# source_eagle.net
KiCad netlist of a schematic drawn in EAGLE
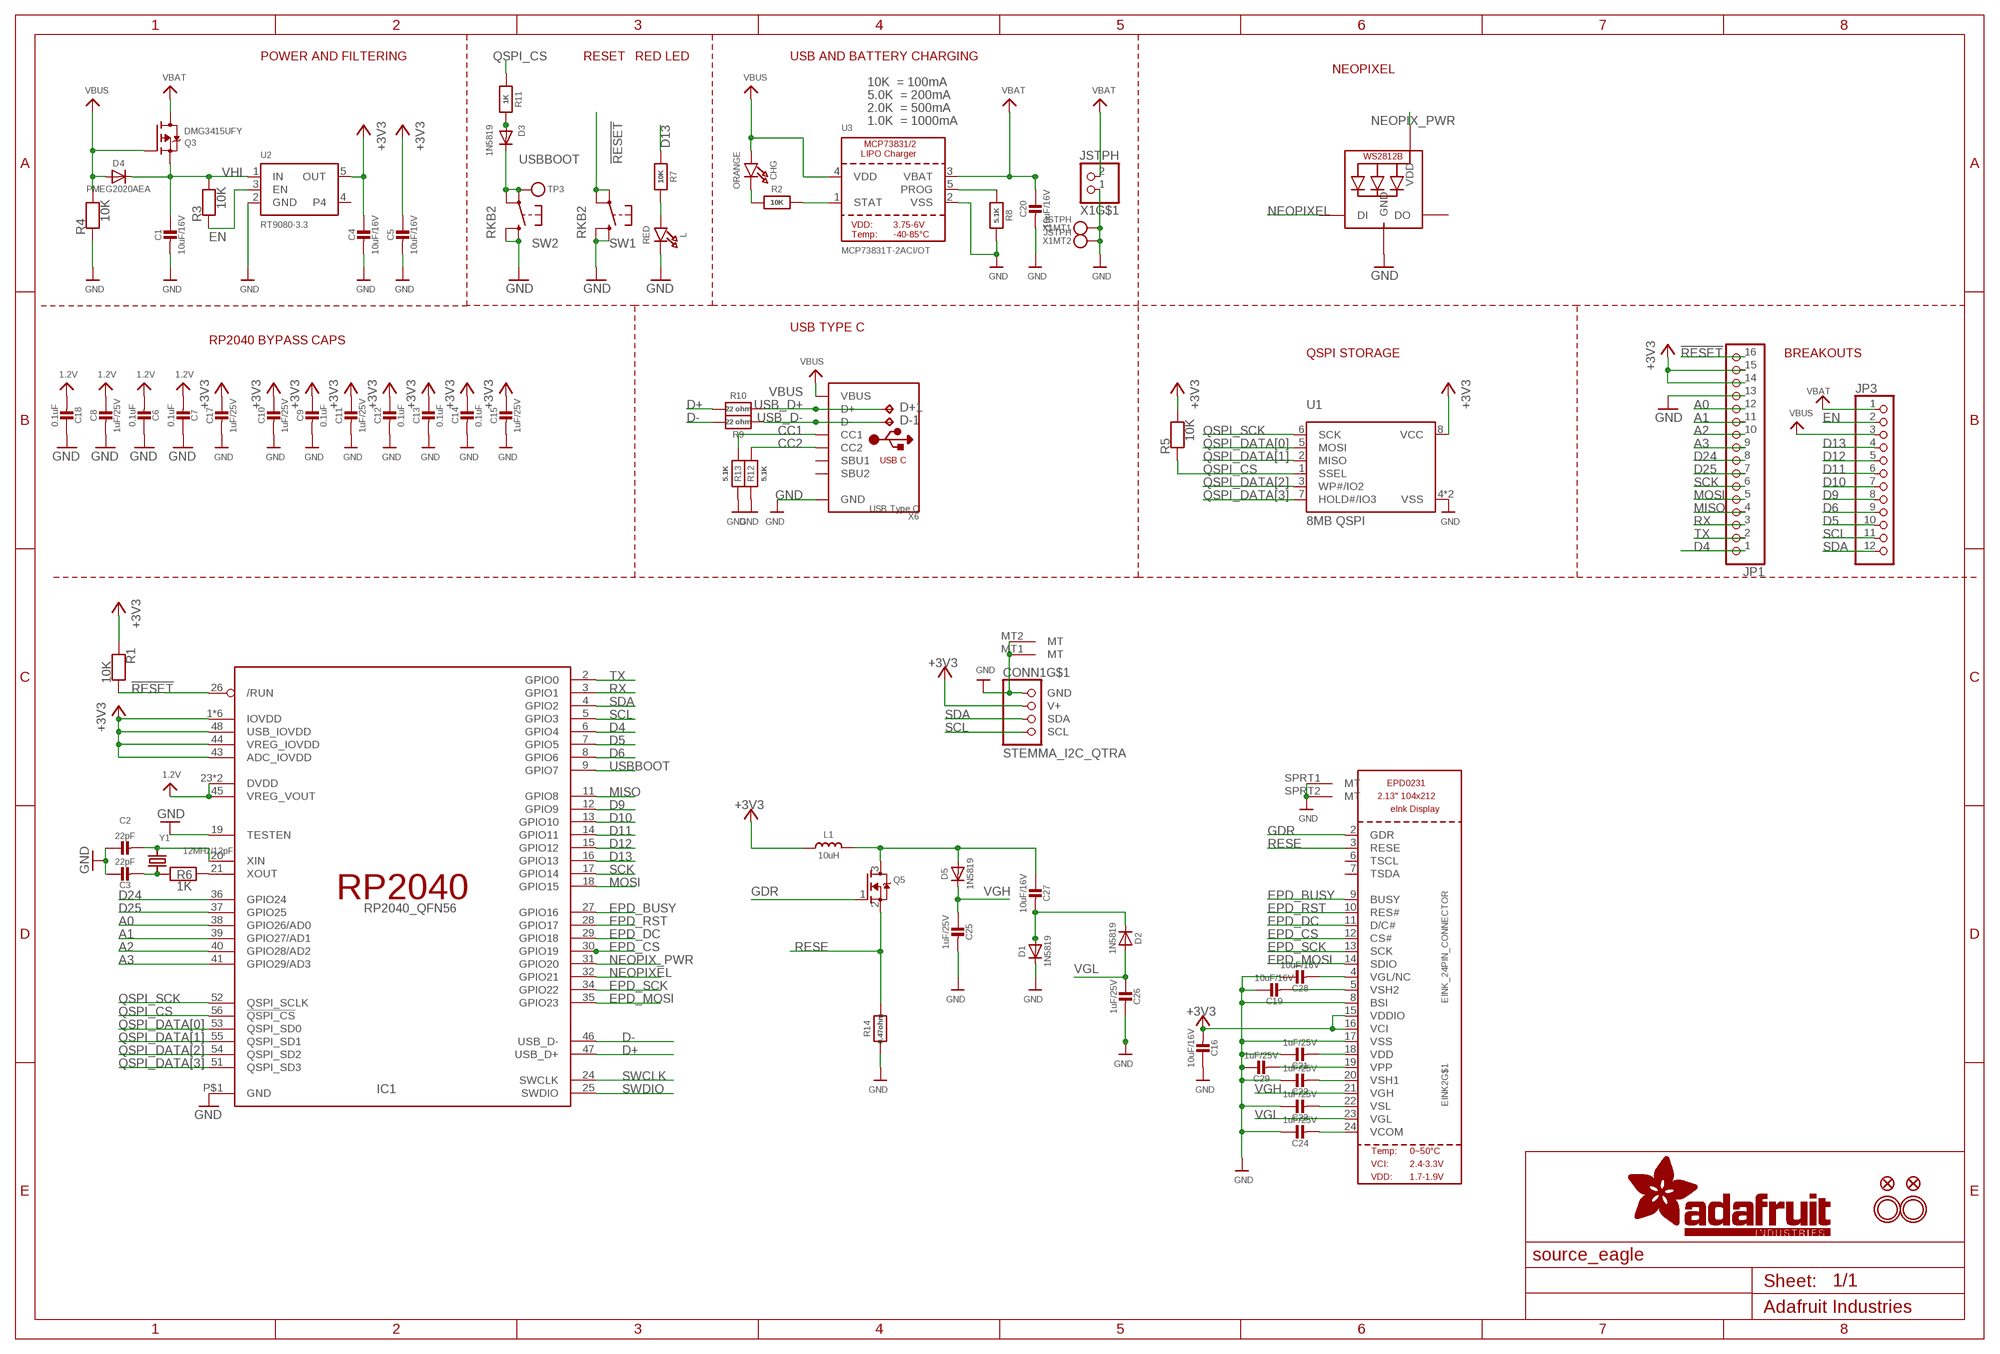
[diagram p0: schematic, sheet 1]

(export (version "E")
  (design (tool "Eeschema 10.0.6"))
  (components
    (comp (ref "C1")
      (value "10uF/16V")
      (footprint "eagle-import:0805-NO")
      (libsource (lib "eagle-import") (part "CAP_CERAMIC0805-NOOUTLINE"))
    )
    (comp (ref "C2")
      (value "22pF")
      (footprint "eagle-import:_0402NO")
      (libsource (lib "eagle-import") (part "CAP_CERAMIC_0402NO"))
    )
    (comp (ref "C3")
      (value "22pF")
      (footprint "eagle-import:_0402NO")
      (libsource (lib "eagle-import") (part "CAP_CERAMIC_0402NO"))
    )
    (comp (ref "C4")
      (value "10uF/16V")
      (footprint "eagle-import:0805-NO")
      (fields (field (name "REV") "A"))
      (libsource (lib "eagle-import") (part "CAP_CERAMIC0805-NOOUTLINE"))
    )
    (comp (ref "C5")
      (value "10uF/16V")
      (footprint "eagle-import:0805-NO")
      (libsource (lib "eagle-import") (part "CAP_CERAMIC0805-NOOUTLINE"))
    )
    (comp (ref "C6")
      (value "0.1uF")
      (footprint "eagle-import:_0402NO")
      (libsource (lib "eagle-import") (part "CAP_CERAMIC_0402NO"))
    )
    (comp (ref "C7")
      (value "0.1uF")
      (footprint "eagle-import:_0402NO")
      (libsource (lib "eagle-import") (part "CAP_CERAMIC_0402NO"))
    )
    (comp (ref "C8")
      (value "1uF/25V")
      (footprint "eagle-import:_0402NO")
      (libsource (lib "eagle-import") (part "CAP_CERAMIC_0402NO"))
    )
    (comp (ref "C9")
      (value "0.1uF")
      (footprint "eagle-import:_0402NO")
      (libsource (lib "eagle-import") (part "CAP_CERAMIC_0402NO"))
    )
    (comp (ref "C10")
      (value "1uF/25V")
      (footprint "eagle-import:_0402NO")
      (libsource (lib "eagle-import") (part "CAP_CERAMIC_0402NO"))
    )
    (comp (ref "C11")
      (value "1uF/25V")
      (footprint "eagle-import:_0402NO")
      (libsource (lib "eagle-import") (part "CAP_CERAMIC_0402NO"))
    )
    (comp (ref "C12")
      (value "0.1uF")
      (footprint "eagle-import:_0402NO")
      (libsource (lib "eagle-import") (part "CAP_CERAMIC_0402NO"))
    )
    (comp (ref "C13")
      (value "0.1uF")
      (footprint "eagle-import:_0402NO")
      (libsource (lib "eagle-import") (part "CAP_CERAMIC_0402NO"))
    )
    (comp (ref "C14")
      (value "0.1uF")
      (footprint "eagle-import:_0402NO")
      (libsource (lib "eagle-import") (part "CAP_CERAMIC_0402NO"))
    )
    (comp (ref "C15")
      (value "1uF/25V")
      (footprint "eagle-import:_0402NO")
      (libsource (lib "eagle-import") (part "CAP_CERAMIC_0402NO"))
    )
    (comp (ref "C16")
      (value "10uF/16V")
      (footprint "eagle-import:0805-NO")
      (libsource (lib "eagle-import") (part "CAP_CERAMIC0805-NOOUTLINE"))
    )
    (comp (ref "C17")
      (value "1uF/25V")
      (footprint "eagle-import:_0402NO")
      (libsource (lib "eagle-import") (part "CAP_CERAMIC_0402NO"))
    )
    (comp (ref "C18")
      (value "0.1uF")
      (footprint "eagle-import:_0402NO")
      (libsource (lib "eagle-import") (part "CAP_CERAMIC_0402NO"))
    )
    (comp (ref "C19")
      (value "10uF/16V")
      (footprint "eagle-import:0805-NO")
      (libsource (lib "eagle-import") (part "CAP_CERAMIC0805-NOOUTLINE"))
    )
    (comp (ref "C20")
      (value "10uF/16V")
      (footprint "eagle-import:0805-NO")
      (libsource (lib "eagle-import") (part "CAP_CERAMIC0805-NOOUTLINE"))
    )
    (comp (ref "C21")
      (value "1uF/25V")
      (footprint "eagle-import:_0402NO")
      (libsource (lib "eagle-import") (part "CAP_CERAMIC_0402NO"))
    )
    (comp (ref "C22")
      (value "1uF/25V")
      (footprint "eagle-import:_0402NO")
      (libsource (lib "eagle-import") (part "CAP_CERAMIC_0402NO"))
    )
    (comp (ref "C23")
      (value "1uF/25V")
      (footprint "eagle-import:_0402NO")
      (libsource (lib "eagle-import") (part "CAP_CERAMIC_0402NO"))
    )
    (comp (ref "C24")
      (value "1uF/25V")
      (footprint "eagle-import:_0402NO")
      (libsource (lib "eagle-import") (part "CAP_CERAMIC_0402NO"))
    )
    (comp (ref "C25")
      (value "1uF/25V")
      (footprint "eagle-import:_0402NO")
      (libsource (lib "eagle-import") (part "CAP_CERAMIC_0402NO"))
    )
    (comp (ref "C26")
      (value "1uF/25V")
      (footprint "eagle-import:_0402NO")
      (libsource (lib "eagle-import") (part "CAP_CERAMIC_0402NO"))
    )
    (comp (ref "C27")
      (value "10uF/16V")
      (footprint "eagle-import:0805-NO")
      (libsource (lib "eagle-import") (part "CAP_CERAMIC0805-NOOUTLINE"))
    )
    (comp (ref "C28")
      (value "10uF/16V")
      (footprint "eagle-import:0805-NO")
      (libsource (lib "eagle-import") (part "CAP_CERAMIC0805-NOOUTLINE"))
    )
    (comp (ref "C29")
      (value "1uF/25V")
      (footprint "eagle-import:_0402NO")
      (libsource (lib "eagle-import") (part "CAP_CERAMIC_0402NO"))
    )
    (comp (ref "CHG")
      (value "ORANGE")
      (footprint "eagle-import:CHIPLED_0603_NOOUTLINE")
      (libsource (lib "eagle-import") (part "LED0603_NOOUTLINE"))
    )
    (comp (ref "CONN1")
      (value "STEMMA_I2C_QTRA")
      (footprint "eagle-import:JST_SH4_RA")
      (libsource (lib "eagle-import") (part "STEMMA_I2C_QTRA"))
    )
    (comp (ref "D+1")
      (value "TPB1,27")
      (footprint "eagle-import:B1,27")
      (libsource (lib "eagle-import") (part "TPB1,27"))
    )
    (comp (ref "D-1")
      (value "TPB1,27")
      (footprint "eagle-import:B1,27")
      (libsource (lib "eagle-import") (part "TPB1,27"))
    )
    (comp (ref "D1")
      (value "1N5819")
      (footprint "eagle-import:SOD-323_MINI")
      (libsource (lib "eagle-import") (part "DIODE_SOD323MINI"))
    )
    (comp (ref "D2")
      (value "1N5819")
      (footprint "eagle-import:SOD-323_MINI")
      (libsource (lib "eagle-import") (part "DIODE_SOD323MINI"))
    )
    (comp (ref "D3")
      (value "1N5819")
      (footprint "eagle-import:SOD-323_MINI")
      (libsource (lib "eagle-import") (part "DIODE_SOD323MINI"))
    )
    (comp (ref "D4")
      (value "PMEG2020AEA")
      (footprint "eagle-import:SOD-323F")
      (libsource (lib "eagle-import") (part "DIODESOD-323F"))
    )
    (comp (ref "D5")
      (value "1N5819")
      (footprint "eagle-import:SOD-323_MINI")
      (libsource (lib "eagle-import") (part "DIODE_SOD323MINI"))
    )
    (comp (ref "EINK2")
      (value "EINK_24PIN_CONNECTOR")
      (footprint "eagle-import:EINK_24PIN")
      (libsource (lib "eagle-import") (part "EINK_24PIN_CONNECTOR"))
    )
    (comp (ref "IC1")
      (value "RP2040_QFN56")
      (footprint "eagle-import:QFN56_7MM_REDUCEDEPAD")
      (libsource (lib "eagle-import") (part "RP2040_QFN56"))
    )
    (comp (ref "JP1")
      (value "HEADER-1X16ROUND")
      (footprint "eagle-import:1X16_ROUND")
      (libsource (lib "eagle-import") (part "HEADER-1X16ROUND"))
    )
    (comp (ref "JP3")
      (value "HEADER-1X12")
      (footprint "eagle-import:1X12_ROUND")
      (libsource (lib "eagle-import") (part "HEADER-1X12"))
    )
    (comp (ref "L")
      (value "RED")
      (footprint "eagle-import:CHIPLED_0603_NOOUTLINE")
      (libsource (lib "eagle-import") (part "LED0603_NOOUTLINE"))
    )
    (comp (ref "L1")
      (value "10uH")
      (footprint "eagle-import:INDUCTOR_4X4MM_NR401")
      (libsource (lib "eagle-import") (part "INDUCTORNR401"))
    )
    (comp (ref "LED1")
      (value "WS2812B_SK6805_1515")
      (footprint "eagle-import:SK6805_1515")
      (libsource (lib "eagle-import") (part "WS2812B_SK6805_1515"))
    )
    (comp (ref "Q3")
      (value "DMG3415UFY")
      (footprint "eagle-import:DFN2015-3")
      (libsource (lib "eagle-import") (part "MOSFET-P_DFN2015"))
    )
    (comp (ref "Q5")
      (value "IRLML0100")
      (footprint "eagle-import:SOT23-WIDE")
      (libsource (lib "eagle-import") (part "MOSFET-NWIDE"))
    )
    (comp (ref "R1")
      (value "10K")
      (footprint "eagle-import:_0402NO")
      (libsource (lib "eagle-import") (part "RESISTOR_0402NO"))
    )
    (comp (ref "R2")
      (value "10K")
      (footprint "eagle-import:_0402NO")
      (libsource (lib "eagle-import") (part "RESISTOR_0402NO"))
    )
    (comp (ref "R3")
      (value "10K")
      (footprint "eagle-import:_0402NO")
      (libsource (lib "eagle-import") (part "RESISTOR_0402NO"))
    )
    (comp (ref "R4")
      (value "10K")
      (footprint "eagle-import:_0402NO")
      (libsource (lib "eagle-import") (part "RESISTOR_0402NO"))
    )
    (comp (ref "R5")
      (value "10K")
      (footprint "eagle-import:_0402NO")
      (libsource (lib "eagle-import") (part "RESISTOR_0402NO"))
    )
    (comp (ref "R6")
      (value "1K")
      (footprint "eagle-import:_0402NO")
      (libsource (lib "eagle-import") (part "RESISTOR_0402NO"))
    )
    (comp (ref "R7")
      (value "10K")
      (footprint "eagle-import:_0402NO")
      (libsource (lib "eagle-import") (part "RESISTOR_0402NO"))
    )
    (comp (ref "R8")
      (value "5.1K")
      (footprint "eagle-import:_0402NO")
      (libsource (lib "eagle-import") (part "RESISTOR_0402NO"))
    )
    (comp (ref "R9")
      (value "22 ohm")
      (footprint "eagle-import:_0402NO")
      (libsource (lib "eagle-import") (part "RESISTOR_0402NO"))
    )
    (comp (ref "R10")
      (value "22 ohm")
      (footprint "eagle-import:_0402NO")
      (libsource (lib "eagle-import") (part "RESISTOR_0402NO"))
    )
    (comp (ref "R11")
      (value "1K")
      (footprint "eagle-import:_0402NO")
      (libsource (lib "eagle-import") (part "RESISTOR_0402NO"))
    )
    (comp (ref "R12")
      (value "5.1K")
      (footprint "eagle-import:_0402NO")
      (libsource (lib "eagle-import") (part "RESISTOR_0402NO"))
    )
    (comp (ref "R13")
      (value "5.1K")
      (footprint "eagle-import:_0402NO")
      (libsource (lib "eagle-import") (part "RESISTOR_0402NO"))
    )
    (comp (ref "R14")
      (value "0.47ohm")
      (footprint "eagle-import:0603-NO")
      (libsource (lib "eagle-import") (part "RESISTOR_0603_NOOUT"))
    )
    (comp (ref "SW1")
      (value "RKB2")
      (footprint "eagle-import:BTN_RKB2_4.6X2.8")
      (libsource (lib "eagle-import") (part "SWITCH_TACT_SMT_RKB2"))
    )
    (comp (ref "SW2")
      (value "RKB2")
      (footprint "eagle-import:BTN_RKB2_4.6X2.8")
      (libsource (lib "eagle-import") (part "SWITCH_TACT_SMT_RKB2"))
    )
    (comp (ref "TP3")
      (value "TESTPOINTROUND1.5MMNO")
      (footprint "eagle-import:TESTPOINT_ROUND_1.5MM_NO")
      (libsource (lib "eagle-import") (part "TESTPOINTROUND1.5MMNO"))
    )
    (comp (ref "U$31")
      (value "MOUNTINGHOLE2.5")
      (footprint "eagle-import:MOUNTINGHOLE_2.5_PLATED")
      (libsource (lib "eagle-import") (part "MOUNTINGHOLE2.5"))
    )
    (comp (ref "U$32")
      (value "MOUNTINGHOLE2.5")
      (footprint "eagle-import:MOUNTINGHOLE_2.5_PLATED")
      (libsource (lib "eagle-import") (part "MOUNTINGHOLE2.5"))
    )
    (comp (ref "U$34")
      (value "FIDUCIAL_1MM")
      (footprint "eagle-import:FIDUCIAL_1MM")
      (libsource (lib "eagle-import") (part "FIDUCIAL_1MM"))
    )
    (comp (ref "U$35")
      (value "FIDUCIAL_1MM")
      (footprint "eagle-import:FIDUCIAL_1MM")
      (libsource (lib "eagle-import") (part "FIDUCIAL_1MM"))
    )
    (comp (ref "U1")
      (value "8MB QSPI")
      (footprint "eagle-import:USON8_4X4")
      (libsource (lib "eagle-import") (part "SPIFLASH_8PIN_4X4"))
    )
    (comp (ref "U2")
      (value "RT9080-3.3")
      (footprint "eagle-import:SOT23-5")
      (fields (field (name "JLC_ROTATION") "0"))
      (libsource (lib "eagle-import") (part "VREG_SOT23-5"))
    )
    (comp (ref "U3")
      (value "MCP73831T-2ACI/OT")
      (footprint "eagle-import:SOT23-5")
      (libsource (lib "eagle-import") (part "MCP73831/2"))
    )
    (comp (ref "X1")
      (value "JSTPH")
      (footprint "eagle-import:JSTPH2_BATT")
      (libsource (lib "eagle-import") (part "CON_JST_PH_2PIN_MT_BATT"))
    )
    (comp (ref "X6")
      (value "USB Type C")
      (footprint "eagle-import:USB_C_CUSB31-CFM2AX-01-X")
      (libsource (lib "eagle-import") (part "USB_C"))
    )
    (comp (ref "Y1")
      (value "12MHz/12pF")
      (footprint "eagle-import:CRYSTAL_2.5X2")
      (libsource (lib "eagle-import") (part "CRYSTAL2.5X2.0"))
    )
  )
  (nets
    (net (code "1") (name "+3V3") (class "Default")
      (node (ref "C10") (pin "1") (pinfunction "1_1") (pintype "passive"))
      (node (ref "C11") (pin "1") (pinfunction "1_1") (pintype "passive"))
      (node (ref "C12") (pin "1") (pinfunction "1_1") (pintype "passive"))
      (node (ref "C13") (pin "1") (pinfunction "1_1") (pintype "passive"))
      (node (ref "C14") (pin "1") (pinfunction "1_1") (pintype "passive"))
      (node (ref "C15") (pin "1") (pinfunction "1_1") (pintype "passive"))
      (node (ref "C16") (pin "2") (pinfunction "2_2") (pintype "passive"))
      (node (ref "C17") (pin "1") (pinfunction "1_1") (pintype "passive"))
      (node (ref "C4") (pin "1") (pinfunction "1_1") (pintype "passive"))
      (node (ref "C5") (pin "1") (pinfunction "1_1") (pintype "passive"))
      (node (ref "C9") (pin "1") (pinfunction "1_1") (pintype "passive"))
      (node (ref "CONN1") (pin "2") (pinfunction "V+_2") (pintype "passive"))
      (node (ref "EINK2") (pin "15") (pinfunction "VDDIO_15") (pintype "power_in"))
      (node (ref "EINK2") (pin "16") (pinfunction "VCI_16") (pintype "power_in"))
      (node (ref "IC1") (pin "1") (pinfunction "IOVDD_1") (pintype "power_in"))
      (node (ref "IC1") (pin "10") (pinfunction "IOVDD_10") (pintype "power_in"))
      (node (ref "IC1") (pin "22") (pinfunction "IOVDD_22") (pintype "power_in"))
      (node (ref "IC1") (pin "33") (pinfunction "IOVDD_33") (pintype "power_in"))
      (node (ref "IC1") (pin "42") (pinfunction "IOVDD_42") (pintype "power_in"))
      (node (ref "IC1") (pin "43") (pinfunction "ADC_IOVDD_43") (pintype "power_in"))
      (node (ref "IC1") (pin "44") (pinfunction "VREG_IOVDD_44") (pintype "power_in"))
      (node (ref "IC1") (pin "48") (pinfunction "USB_IOVDD_48") (pintype "power_in"))
      (node (ref "IC1") (pin "49") (pinfunction "IOVDD_49") (pintype "power_in"))
      (node (ref "JP1") (pin "14") (pinfunction "14_14") (pintype "passive"))
      (node (ref "JP1") (pin "15") (pinfunction "15_15") (pintype "passive"))
      (node (ref "L1") (pin "P$2") (pinfunction "2_P$2") (pintype "passive"))
      (node (ref "R1") (pin "1") (pinfunction "1_1") (pintype "passive"))
      (node (ref "R5") (pin "2") (pinfunction "2_2") (pintype "passive"))
      (node (ref "U1") (pin "8") (pinfunction "VCC_8") (pintype "bidirectional"))
      (node (ref "U2") (pin "5") (pinfunction "OUT_5") (pintype "power_in"))
    )
    (net (code "2") (name "/A0") (class "Default")
      (node (ref "IC1") (pin "38") (pinfunction "GPIO26/AD0_38") (pintype "bidirectional"))
      (node (ref "JP1") (pin "12") (pinfunction "12_12") (pintype "passive"))
    )
    (net (code "3") (name "/A1") (class "Default")
      (node (ref "IC1") (pin "39") (pinfunction "GPIO27/AD1_39") (pintype "bidirectional"))
      (node (ref "JP1") (pin "11") (pinfunction "11_11") (pintype "passive"))
    )
    (net (code "4") (name "/A2") (class "Default")
      (node (ref "IC1") (pin "40") (pinfunction "GPIO28/AD2_40") (pintype "bidirectional"))
      (node (ref "JP1") (pin "10") (pinfunction "10_10") (pintype "passive"))
    )
    (net (code "5") (name "/A3") (class "Default")
      (node (ref "IC1") (pin "41") (pinfunction "GPIO29/AD3_41") (pintype "bidirectional"))
      (node (ref "JP1") (pin "9") (pinfunction "9_9") (pintype "passive"))
    )
    (net (code "6") (name "/CC1") (class "Default")
      (node (ref "R13") (pin "2") (pinfunction "2_2") (pintype "passive"))
      (node (ref "X6") (pin "A5") (pinfunction "CC1_A5") (pintype "bidirectional"))
    )
    (net (code "7") (name "/CC2") (class "Default")
      (node (ref "R12") (pin "2") (pinfunction "2_2") (pintype "passive"))
      (node (ref "X6") (pin "B5") (pinfunction "CC2_B5") (pintype "bidirectional"))
    )
    (net (code "8") (name "/D+") (class "Default")
      (node (ref "IC1") (pin "47") (pinfunction "USB_D+_47") (pintype "bidirectional"))
      (node (ref "R10") (pin "2") (pinfunction "2_2") (pintype "passive"))
    )
    (net (code "9") (name "/D-") (class "Default")
      (node (ref "IC1") (pin "46") (pinfunction "USB_D-_46") (pintype "bidirectional"))
      (node (ref "R9") (pin "2") (pinfunction "2_2") (pintype "passive"))
    )
    (net (code "10") (name "/D4") (class "Default")
      (node (ref "IC1") (pin "6") (pinfunction "GPIO4_6") (pintype "bidirectional"))
      (node (ref "JP1") (pin "1") (pinfunction "1_1") (pintype "passive"))
    )
    (net (code "11") (name "/D5") (class "Default")
      (node (ref "IC1") (pin "7") (pinfunction "GPIO5_7") (pintype "bidirectional"))
      (node (ref "JP3") (pin "10") (pinfunction "10_10") (pintype "passive"))
    )
    (net (code "12") (name "/D6") (class "Default")
      (node (ref "IC1") (pin "8") (pinfunction "GPIO6_8") (pintype "bidirectional"))
      (node (ref "JP3") (pin "9") (pinfunction "9_9") (pintype "passive"))
    )
    (net (code "13") (name "/D9") (class "Default")
      (node (ref "IC1") (pin "12") (pinfunction "GPIO9_12") (pintype "bidirectional"))
      (node (ref "JP3") (pin "8") (pinfunction "8_8") (pintype "passive"))
    )
    (net (code "14") (name "/D10") (class "Default")
      (node (ref "IC1") (pin "13") (pinfunction "GPIO10_13") (pintype "bidirectional"))
      (node (ref "JP3") (pin "7") (pinfunction "7_7") (pintype "passive"))
    )
    (net (code "15") (name "/D11") (class "Default")
      (node (ref "IC1") (pin "14") (pinfunction "GPIO11_14") (pintype "bidirectional"))
      (node (ref "JP3") (pin "6") (pinfunction "6_6") (pintype "passive"))
    )
    (net (code "16") (name "/D12") (class "Default")
      (node (ref "IC1") (pin "15") (pinfunction "GPIO12_15") (pintype "bidirectional"))
      (node (ref "JP3") (pin "5") (pinfunction "5_5") (pintype "passive"))
    )
    (net (code "17") (name "/D13") (class "Default")
      (node (ref "IC1") (pin "16") (pinfunction "GPIO13_16") (pintype "bidirectional"))
      (node (ref "JP3") (pin "4") (pinfunction "4_4") (pintype "passive"))
      (node (ref "R7") (pin "1") (pinfunction "1_1") (pintype "passive"))
    )
    (net (code "18") (name "/D24") (class "Default")
      (node (ref "IC1") (pin "36") (pinfunction "GPIO24_36") (pintype "bidirectional"))
      (node (ref "JP1") (pin "8") (pinfunction "8_8") (pintype "passive"))
    )
    (net (code "19") (name "/D25") (class "Default")
      (node (ref "IC1") (pin "37") (pinfunction "GPIO25_37") (pintype "bidirectional"))
      (node (ref "JP1") (pin "7") (pinfunction "7_7") (pintype "passive"))
    )
    (net (code "20") (name "/EN") (class "Default")
      (node (ref "JP3") (pin "2") (pinfunction "2_2") (pintype "passive"))
      (node (ref "R3") (pin "1") (pinfunction "1_1") (pintype "passive"))
      (node (ref "U2") (pin "3") (pinfunction "EN_3") (pintype "input"))
    )
    (net (code "21") (name "/EPD_BUSY") (class "Default")
      (node (ref "EINK2") (pin "9") (pinfunction "BUSY_9") (pintype "output"))
      (node (ref "IC1") (pin "27") (pinfunction "GPIO16_27") (pintype "bidirectional"))
    )
    (net (code "22") (name "/EPD_CS") (class "Default")
      (node (ref "EINK2") (pin "12") (pinfunction "CS#_12") (pintype "input"))
      (node (ref "IC1") (pin "30") (pinfunction "GPIO19_30") (pintype "bidirectional"))
    )
    (net (code "23") (name "/EPD_DC") (class "Default")
      (node (ref "EINK2") (pin "11") (pinfunction "D/C#_11") (pintype "input"))
      (node (ref "IC1") (pin "29") (pinfunction "GPIO18_29") (pintype "bidirectional"))
    )
    (net (code "24") (name "/EPD_MOSI") (class "Default")
      (node (ref "EINK2") (pin "14") (pinfunction "SDIO_14") (pintype "bidirectional"))
      (node (ref "IC1") (pin "35") (pinfunction "GPIO23_35") (pintype "bidirectional"))
    )
    (net (code "25") (name "/EPD_RST") (class "Default")
      (node (ref "EINK2") (pin "10") (pinfunction "RES#_10") (pintype "input"))
      (node (ref "IC1") (pin "28") (pinfunction "GPIO17_28") (pintype "bidirectional"))
    )
    (net (code "26") (name "/EPD_SCK") (class "Default")
      (node (ref "EINK2") (pin "13") (pinfunction "SCK_13") (pintype "bidirectional"))
      (node (ref "IC1") (pin "34") (pinfunction "GPIO22_34") (pintype "bidirectional"))
    )
    (net (code "27") (name "/GDR") (class "Default")
      (node (ref "EINK2") (pin "2") (pinfunction "GDR_2") (pintype "output"))
      (node (ref "Q5") (pin "1") (pinfunction "G_1") (pintype "bidirectional"))
    )
    (net (code "28") (name "/MISO") (class "Default")
      (node (ref "IC1") (pin "11") (pinfunction "GPIO8_11") (pintype "bidirectional"))
      (node (ref "JP1") (pin "4") (pinfunction "4_4") (pintype "passive"))
    )
    (net (code "29") (name "/MOSI") (class "Default")
      (node (ref "IC1") (pin "18") (pinfunction "GPIO15_18") (pintype "bidirectional"))
      (node (ref "JP1") (pin "5") (pinfunction "5_5") (pintype "passive"))
    )
    (net (code "30") (name "/NEOPIXEL") (class "Default")
      (node (ref "IC1") (pin "32") (pinfunction "GPIO21_32") (pintype "bidirectional"))
      (node (ref "LED1") (pin "1") (pinfunction "DI_1") (pintype "input"))
    )
    (net (code "31") (name "/NEOPIX_PWR") (class "Default")
      (node (ref "IC1") (pin "31") (pinfunction "GPIO20_31") (pintype "bidirectional"))
      (node (ref "LED1") (pin "2") (pinfunction "VDD_2") (pintype "power_in"))
    )
    (net (code "32") (name "/QSPI_CS") (class "Default")
      (node (ref "IC1") (pin "56") (pinfunction "~{QSPI_CS}_56") (pintype "bidirectional"))
      (node (ref "R11") (pin "1") (pinfunction "1_1") (pintype "passive"))
      (node (ref "R5") (pin "1") (pinfunction "1_1") (pintype "passive"))
      (node (ref "U1") (pin "1") (pinfunction "SSEL_1") (pintype "bidirectional"))
    )
    (net (code "33") (name "/QSPI_DATA[0]") (class "Default")
      (node (ref "IC1") (pin "53") (pinfunction "QSPI_SD0_53") (pintype "bidirectional"))
      (node (ref "U1") (pin "5") (pinfunction "MOSI_5") (pintype "bidirectional"))
    )
    (net (code "34") (name "/QSPI_DATA[1]") (class "Default")
      (node (ref "IC1") (pin "55") (pinfunction "QSPI_SD1_55") (pintype "bidirectional"))
      (node (ref "U1") (pin "2") (pinfunction "MISO_2") (pintype "bidirectional"))
    )
    (net (code "35") (name "/QSPI_DATA[2]") (class "Default")
      (node (ref "IC1") (pin "54") (pinfunction "QSPI_SD2_54") (pintype "bidirectional"))
      (node (ref "U1") (pin "3") (pinfunction "WP#/IO2_3") (pintype "bidirectional"))
    )
    (net (code "36") (name "/QSPI_DATA[3]") (class "Default")
      (node (ref "IC1") (pin "51") (pinfunction "QSPI_SD3_51") (pintype "bidirectional"))
      (node (ref "U1") (pin "7") (pinfunction "HOLD#/IO3_7") (pintype "bidirectional"))
    )
    (net (code "37") (name "/QSPI_SCK") (class "Default")
      (node (ref "IC1") (pin "52") (pinfunction "QSPI_SCLK_52") (pintype "bidirectional"))
      (node (ref "U1") (pin "6") (pinfunction "SCK_6") (pintype "bidirectional"))
    )
    (net (code "38") (name "/RESE") (class "Default")
      (node (ref "EINK2") (pin "3") (pinfunction "RESE_3") (pintype "input"))
      (node (ref "Q5") (pin "2") (pinfunction "S_2") (pintype "bidirectional"))
      (node (ref "R14") (pin "1") (pinfunction "1_1") (pintype "passive"))
    )
    (net (code "39") (name "/RX") (class "Default")
      (node (ref "IC1") (pin "3") (pinfunction "GPIO1_3") (pintype "bidirectional"))
      (node (ref "JP1") (pin "3") (pinfunction "3_3") (pintype "passive"))
    )
    (net (code "40") (name "/SCK") (class "Default")
      (node (ref "IC1") (pin "17") (pinfunction "GPIO14_17") (pintype "bidirectional"))
      (node (ref "JP1") (pin "6") (pinfunction "6_6") (pintype "passive"))
    )
    (net (code "41") (name "/SCL") (class "Default")
      (node (ref "CONN1") (pin "4") (pinfunction "SCL_4") (pintype "passive"))
      (node (ref "IC1") (pin "5") (pinfunction "GPIO3_5") (pintype "bidirectional"))
      (node (ref "JP3") (pin "11") (pinfunction "11_11") (pintype "passive"))
    )
    (net (code "42") (name "/SDA") (class "Default")
      (node (ref "CONN1") (pin "3") (pinfunction "SDA_3") (pintype "passive"))
      (node (ref "IC1") (pin "4") (pinfunction "GPIO2_4") (pintype "bidirectional"))
      (node (ref "JP3") (pin "12") (pinfunction "12_12") (pintype "passive"))
    )
    (net (code "43") (name "/SWCLK") (class "Default")
      (node (ref "IC1") (pin "24") (pinfunction "SWCLK_24") (pintype "bidirectional"))
    )
    (net (code "44") (name "/SWDIO") (class "Default")
      (node (ref "IC1") (pin "25") (pinfunction "SWDIO_25") (pintype "bidirectional"))
    )
    (net (code "45") (name "/TX") (class "Default")
      (node (ref "IC1") (pin "2") (pinfunction "GPIO0_2") (pintype "bidirectional"))
      (node (ref "JP1") (pin "2") (pinfunction "2_2") (pintype "passive"))
    )
    (net (code "46") (name "/USBBOOT") (class "Default")
      (node (ref "D3") (pin "C") (pinfunction "C_C") (pintype "passive"))
      (node (ref "IC1") (pin "9") (pinfunction "GPIO7_9") (pintype "bidirectional"))
      (node (ref "SW2") (pin "A") (pinfunction "P_A") (pintype "passive"))
      (node (ref "SW2") (pin "A'") (pinfunction "P1_A'") (pintype "passive"))
      (node (ref "TP3") (pin "P$1") (pinfunction "P$1_P$1") (pintype "bidirectional"))
    )
    (net (code "47") (name "/USB_D+") (class "Default")
      (node (ref "D+1") (pin "TP") (pinfunction "TP_TP") (pintype "input"))
      (node (ref "R10") (pin "1") (pinfunction "1_1") (pintype "passive"))
      (node (ref "X6") (pin "A6") (pinfunction "D+_A6") (pintype "bidirectional"))
      (node (ref "X6") (pin "B6") (pinfunction "D+_B6") (pintype "bidirectional"))
    )
    (net (code "48") (name "/USB_D-") (class "Default")
      (node (ref "D-1") (pin "TP") (pinfunction "TP_TP") (pintype "input"))
      (node (ref "R9") (pin "1") (pinfunction "1_1") (pintype "passive"))
      (node (ref "X6") (pin "A7") (pinfunction "D-_A7") (pintype "bidirectional"))
      (node (ref "X6") (pin "B7") (pinfunction "D-_B7") (pintype "bidirectional"))
    )
    (net (code "49") (name "/VGH") (class "Default")
      (node (ref "C25") (pin "1") (pinfunction "1_1") (pintype "passive"))
      (node (ref "D5") (pin "C") (pinfunction "C_C") (pintype "passive"))
      (node (ref "EINK2") (pin "21") (pinfunction "VGH_21") (pintype "passive"))
    )
    (net (code "50") (name "/VGL") (class "Default")
      (node (ref "C26") (pin "1") (pinfunction "1_1") (pintype "passive"))
      (node (ref "D2") (pin "A") (pinfunction "A_A") (pintype "passive"))
      (node (ref "EINK2") (pin "23") (pinfunction "VGL_23") (pintype "passive"))
    )
    (net (code "51") (name "/VHI") (class "Default")
      (node (ref "C1") (pin "1") (pinfunction "1_1") (pintype "passive"))
      (node (ref "D4") (pin "C") (pinfunction "C_C") (pintype "passive"))
      (node (ref "Q3") (pin "2") (pinfunction "S_2") (pintype "passive"))
      (node (ref "R3") (pin "2") (pinfunction "2_2") (pintype "passive"))
      (node (ref "U2") (pin "1") (pinfunction "IN_1") (pintype "power_in"))
    )
    (net (code "52") (name "/~{RESET}") (class "Default")
      (node (ref "IC1") (pin "26") (pinfunction "/RUN_26") (pintype "bidirectional"))
      (node (ref "JP1") (pin "16") (pinfunction "16_16") (pintype "passive"))
      (node (ref "R1") (pin "2") (pinfunction "2_2") (pintype "passive"))
      (node (ref "SW1") (pin "A") (pinfunction "P_A") (pintype "passive"))
      (node (ref "SW1") (pin "A'") (pinfunction "P1_A'") (pintype "passive"))
    )
    (net (code "53") (name "1.2V") (class "Default")
      (node (ref "C18") (pin "2") (pinfunction "2_2") (pintype "passive"))
      (node (ref "C6") (pin "2") (pinfunction "2_2") (pintype "passive"))
      (node (ref "C7") (pin "2") (pinfunction "2_2") (pintype "passive"))
      (node (ref "C8") (pin "1") (pinfunction "1_1") (pintype "passive"))
      (node (ref "IC1") (pin "23") (pinfunction "DVDD_23") (pintype "power_in"))
      (node (ref "IC1") (pin "45") (pinfunction "VREG_VOUT_45") (pintype "power_in"))
      (node (ref "IC1") (pin "50") (pinfunction "DVDD_50") (pintype "power_in"))
    )
    (net (code "54") (name "GND") (class "Default")
      (node (ref "C1") (pin "2") (pinfunction "2_2") (pintype "passive"))
      (node (ref "C10") (pin "2") (pinfunction "2_2") (pintype "passive"))
      (node (ref "C11") (pin "2") (pinfunction "2_2") (pintype "passive"))
      (node (ref "C12") (pin "2") (pinfunction "2_2") (pintype "passive"))
      (node (ref "C13") (pin "2") (pinfunction "2_2") (pintype "passive"))
      (node (ref "C14") (pin "2") (pinfunction "2_2") (pintype "passive"))
      (node (ref "C15") (pin "2") (pinfunction "2_2") (pintype "passive"))
      (node (ref "C16") (pin "1") (pinfunction "1_1") (pintype "passive"))
      (node (ref "C17") (pin "2") (pinfunction "2_2") (pintype "passive"))
      (node (ref "C18") (pin "1") (pinfunction "1_1") (pintype "passive"))
      (node (ref "C19") (pin "1") (pinfunction "1_1") (pintype "passive"))
      (node (ref "C2") (pin "1") (pinfunction "1_1") (pintype "passive"))
      (node (ref "C20") (pin "2") (pinfunction "2_2") (pintype "passive"))
      (node (ref "C21") (pin "1") (pinfunction "1_1") (pintype "passive"))
      (node (ref "C22") (pin "1") (pinfunction "1_1") (pintype "passive"))
      (node (ref "C23") (pin "1") (pinfunction "1_1") (pintype "passive"))
      (node (ref "C24") (pin "1") (pinfunction "1_1") (pintype "passive"))
      (node (ref "C25") (pin "2") (pinfunction "2_2") (pintype "passive"))
      (node (ref "C26") (pin "2") (pinfunction "2_2") (pintype "passive"))
      (node (ref "C28") (pin "1") (pinfunction "1_1") (pintype "passive"))
      (node (ref "C29") (pin "1") (pinfunction "1_1") (pintype "passive"))
      (node (ref "C3") (pin "1") (pinfunction "1_1") (pintype "passive"))
      (node (ref "C4") (pin "2") (pinfunction "2_2") (pintype "passive"))
      (node (ref "C5") (pin "2") (pinfunction "2_2") (pintype "passive"))
      (node (ref "C6") (pin "1") (pinfunction "1_1") (pintype "passive"))
      (node (ref "C7") (pin "1") (pinfunction "1_1") (pintype "passive"))
      (node (ref "C8") (pin "2") (pinfunction "2_2") (pintype "passive"))
      (node (ref "C9") (pin "2") (pinfunction "2_2") (pintype "passive"))
      (node (ref "CONN1") (pin "1") (pinfunction "GND_1") (pintype "passive"))
      (node (ref "CONN1") (pin "MT1") (pinfunction "MT_MT1") (pintype "bidirectional"))
      (node (ref "CONN1") (pin "MT2") (pinfunction "MT_MT2") (pintype "bidirectional"))
      (node (ref "D1") (pin "C") (pinfunction "C_C") (pintype "passive"))
      (node (ref "EINK2") (pin "17") (pinfunction "VSS_17") (pintype "power_in"))
      (node (ref "EINK2") (pin "8") (pinfunction "BSI_8") (pintype "input"))
      (node (ref "EINK2") (pin "SPRT1") (pinfunction "MT_SPRT1") (pintype "bidirectional"))
      (node (ref "EINK2") (pin "SPRT2") (pinfunction "MT_SPRT2") (pintype "bidirectional"))
      (node (ref "IC1") (pin "19") (pinfunction "TESTEN_19") (pintype "input"))
      (node (ref "IC1") (pin "P$1") (pinfunction "GND_P$1") (pintype "power_in"))
      (node (ref "JP1") (pin "13") (pinfunction "13_13") (pintype "passive"))
      (node (ref "L") (pin "C") (pinfunction "C_C") (pintype "passive"))
      (node (ref "LED1") (pin "4") (pinfunction "GND_4") (pintype "power_in"))
      (node (ref "R12") (pin "1") (pinfunction "1_1") (pintype "passive"))
      (node (ref "R13") (pin "1") (pinfunction "1_1") (pintype "passive"))
      (node (ref "R14") (pin "2") (pinfunction "2_2") (pintype "passive"))
      (node (ref "R4") (pin "1") (pinfunction "1_1") (pintype "passive"))
      (node (ref "R8") (pin "2") (pinfunction "2_2") (pintype "passive"))
      (node (ref "SW1") (pin "B") (pinfunction "S_B") (pintype "passive"))
      (node (ref "SW1") (pin "B'") (pinfunction "S1_B'") (pintype "passive"))
      (node (ref "SW2") (pin "B") (pinfunction "S_B") (pintype "passive"))
      (node (ref "SW2") (pin "B'") (pinfunction "S1_B'") (pintype "passive"))
      (node (ref "U1") (pin "4") (pinfunction "VSS_4") (pintype "bidirectional"))
      (node (ref "U1") (pin "PAD") (pinfunction "VSS_PAD") (pintype "bidirectional"))
      (node (ref "U2") (pin "2") (pinfunction "GND_2") (pintype "power_in"))
      (node (ref "U3") (pin "2") (pinfunction "VSS_2") (pintype "power_in"))
      (node (ref "X1") (pin "1") (pinfunction "1_1") (pintype "passive"))
      (node (ref "X1") (pin "NC1") (pinfunction "P$1_NC1") (pintype "bidirectional"))
      (node (ref "X1") (pin "NC2") (pinfunction "P$1_NC2") (pintype "bidirectional"))
      (node (ref "X6") (pin "A1B12") (pinfunction "GND_A1B12") (pintype "power_in"))
      (node (ref "X6") (pin "B1A12") (pinfunction "GND_B1A12") (pintype "power_in"))
    )
    (net (code "55") (name "Net-(C3-Pad2)") (class "Default")
      (node (ref "C3") (pin "2") (pinfunction "2_2") (pintype "passive"))
      (node (ref "R6") (pin "1") (pinfunction "1_1") (pintype "passive"))
      (node (ref "Y1") (pin "1") (pinfunction "1_1") (pintype "passive"))
    )
    (net (code "56") (name "Net-(C27-Pad2)") (class "Default")
      (node (ref "C27") (pin "2") (pinfunction "2_2") (pintype "passive"))
      (node (ref "D1") (pin "A") (pinfunction "A_A") (pintype "passive"))
      (node (ref "D2") (pin "C") (pinfunction "C_C") (pintype "passive"))
    )
    (net (code "57") (name "Net-(CHG-PadC)") (class "Default")
      (node (ref "CHG") (pin "C") (pinfunction "C_C") (pintype "passive"))
      (node (ref "R2") (pin "1") (pinfunction "1_1") (pintype "passive"))
    )
    (net (code "58") (name "Net-(D3-PadA)") (class "Default")
      (node (ref "D3") (pin "A") (pinfunction "A_A") (pintype "passive"))
      (node (ref "R11") (pin "2") (pinfunction "2_2") (pintype "passive"))
    )
    (net (code "59") (name "Net-(EINK2A-VCOM)") (class "Default")
      (node (ref "C24") (pin "2") (pinfunction "2_2") (pintype "passive"))
      (node (ref "EINK2") (pin "24") (pinfunction "VCOM_24") (pintype "passive"))
    )
    (net (code "60") (name "Net-(EINK2A-VDD)") (class "Default")
      (node (ref "C21") (pin "2") (pinfunction "2_2") (pintype "passive"))
      (node (ref "EINK2") (pin "18") (pinfunction "VDD_18") (pintype "passive"))
    )
    (net (code "61") (name "Net-(EINK2A-VGL{slash}NC)") (class "Default")
      (node (ref "C28") (pin "2") (pinfunction "2_2") (pintype "passive"))
      (node (ref "EINK2") (pin "4") (pinfunction "VGL/NC_4") (pintype "bidirectional"))
    )
    (net (code "62") (name "Net-(EINK2A-VPP)") (class "Default")
      (node (ref "C29") (pin "2") (pinfunction "2_2") (pintype "passive"))
      (node (ref "EINK2") (pin "19") (pinfunction "VPP_19") (pintype "passive"))
    )
    (net (code "63") (name "Net-(EINK2A-VSH1)") (class "Default")
      (node (ref "C22") (pin "2") (pinfunction "2_2") (pintype "passive"))
      (node (ref "EINK2") (pin "20") (pinfunction "VSH1_20") (pintype "passive"))
    )
    (net (code "64") (name "Net-(EINK2A-VSH2)") (class "Default")
      (node (ref "C19") (pin "2") (pinfunction "2_2") (pintype "passive"))
      (node (ref "EINK2") (pin "5") (pinfunction "VSH2_5") (pintype "passive"))
    )
    (net (code "65") (name "Net-(EINK2A-VSL)") (class "Default")
      (node (ref "C23") (pin "2") (pinfunction "2_2") (pintype "passive"))
      (node (ref "EINK2") (pin "22") (pinfunction "VSL_22") (pintype "passive"))
    )
    (net (code "66") (name "Net-(IC1-XIN)") (class "Default")
      (node (ref "C2") (pin "2") (pinfunction "2_2") (pintype "passive"))
      (node (ref "IC1") (pin "20") (pinfunction "XIN_20") (pintype "input"))
      (node (ref "Y1") (pin "3") (pinfunction "2_3") (pintype "passive"))
    )
    (net (code "67") (name "Net-(IC1-XOUT)") (class "Default")
      (node (ref "IC1") (pin "21") (pinfunction "XOUT_21") (pintype "output"))
      (node (ref "R6") (pin "2") (pinfunction "2_2") (pintype "passive"))
    )
    (net (code "68") (name "Net-(L-PadA)") (class "Default")
      (node (ref "L") (pin "A") (pinfunction "A_A") (pintype "passive"))
      (node (ref "R7") (pin "2") (pinfunction "2_2") (pintype "passive"))
    )
    (net (code "69") (name "Net-(L1-1)") (class "Default")
      (node (ref "C27") (pin "1") (pinfunction "1_1") (pintype "passive"))
      (node (ref "D5") (pin "A") (pinfunction "A_A") (pintype "passive"))
      (node (ref "L1") (pin "P$1") (pinfunction "1_P$1") (pintype "passive"))
      (node (ref "Q5") (pin "3") (pinfunction "D_3") (pintype "bidirectional"))
    )
    (net (code "70") (name "Net-(U3-PROG)") (class "Default")
      (node (ref "R8") (pin "1") (pinfunction "1_1") (pintype "passive"))
      (node (ref "U3") (pin "5") (pinfunction "PROG_5") (pintype "input"))
    )
    (net (code "71") (name "Net-(U3-STAT)") (class "Default")
      (node (ref "R2") (pin "2") (pinfunction "2_2") (pintype "passive"))
      (node (ref "U3") (pin "1") (pinfunction "STAT_1") (pintype "output"))
    )
    (net (code "72") (name "VBAT") (class "Default")
      (node (ref "C20") (pin "1") (pinfunction "1_1") (pintype "passive"))
      (node (ref "JP3") (pin "1") (pinfunction "1_1") (pintype "passive"))
      (node (ref "Q3") (pin "3") (pinfunction "D_3") (pintype "passive"))
      (node (ref "U3") (pin "3") (pinfunction "VBAT_3") (pintype "power_in"))
      (node (ref "X1") (pin "2") (pinfunction "2_2") (pintype "passive"))
    )
    (net (code "73") (name "VBUS") (class "Default")
      (node (ref "CHG") (pin "A") (pinfunction "A_A") (pintype "passive"))
      (node (ref "D4") (pin "A") (pinfunction "A_A") (pintype "passive"))
      (node (ref "JP3") (pin "3") (pinfunction "3_3") (pintype "passive"))
      (node (ref "Q3") (pin "1") (pinfunction "G_1") (pintype "passive"))
      (node (ref "R4") (pin "2") (pinfunction "2_2") (pintype "passive"))
      (node (ref "U3") (pin "4") (pinfunction "VDD_4") (pintype "power_in"))
      (node (ref "X6") (pin "A4B9") (pinfunction "VBUS_A4B9") (pintype "power_in"))
      (node (ref "X6") (pin "B4A9") (pinfunction "VBUS_B4A9") (pintype "power_in"))
    )
    (net (code "74") (name "unconnected-(EINK2A-TSCL-Pad6)") (class "Default")
      (node (ref "EINK2") (pin "6") (pinfunction "TSCL_6") (pintype "output"))
    )
    (net (code "75") (name "unconnected-(EINK2A-TSDA-Pad7)") (class "Default")
      (node (ref "EINK2") (pin "7") (pinfunction "TSDA_7") (pintype "bidirectional"))
    )
    (net (code "76") (name "unconnected-(LED1-DO-Pad3)") (class "Default")
      (node (ref "LED1") (pin "3") (pinfunction "DO_3") (pintype "output"))
    )
    (net (code "77") (name "unconnected-(U2-P4-Pad4)") (class "Default")
      (node (ref "U2") (pin "4") (pinfunction "P4_4") (pintype "bidirectional"))
    )
    (net (code "78") (name "unconnected-(X6-SBU1-PadA8)") (class "Default")
      (node (ref "X6") (pin "A8") (pinfunction "SBU1_A8") (pintype "bidirectional"))
    )
    (net (code "79") (name "unconnected-(X6-SBU2-PadB8)") (class "Default")
      (node (ref "X6") (pin "B8") (pinfunction "SBU2_B8") (pintype "bidirectional"))
    )
  )
)
